# vcf.net
KiCad netlist of a schematic drawn in EAGLE
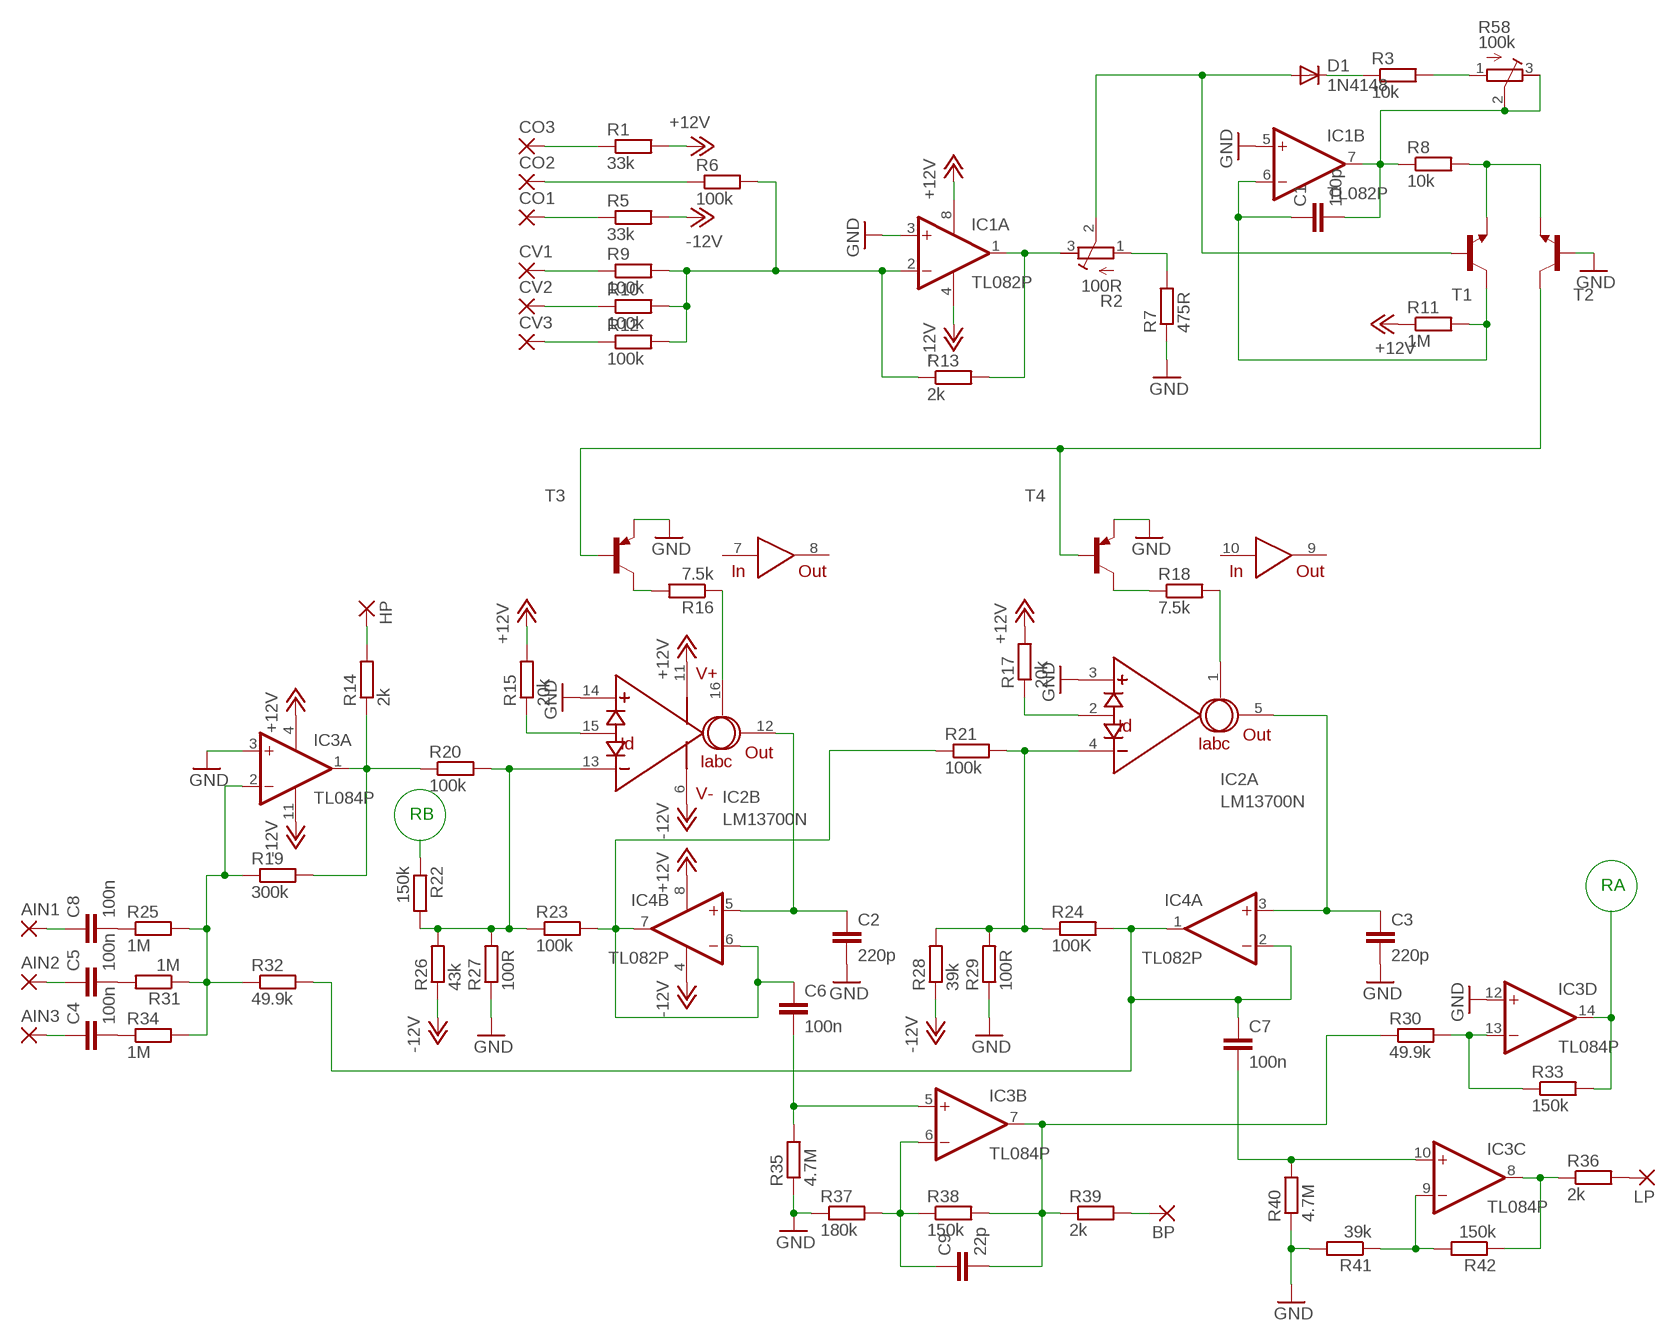
[diagram p0: schematic, sheet 1]
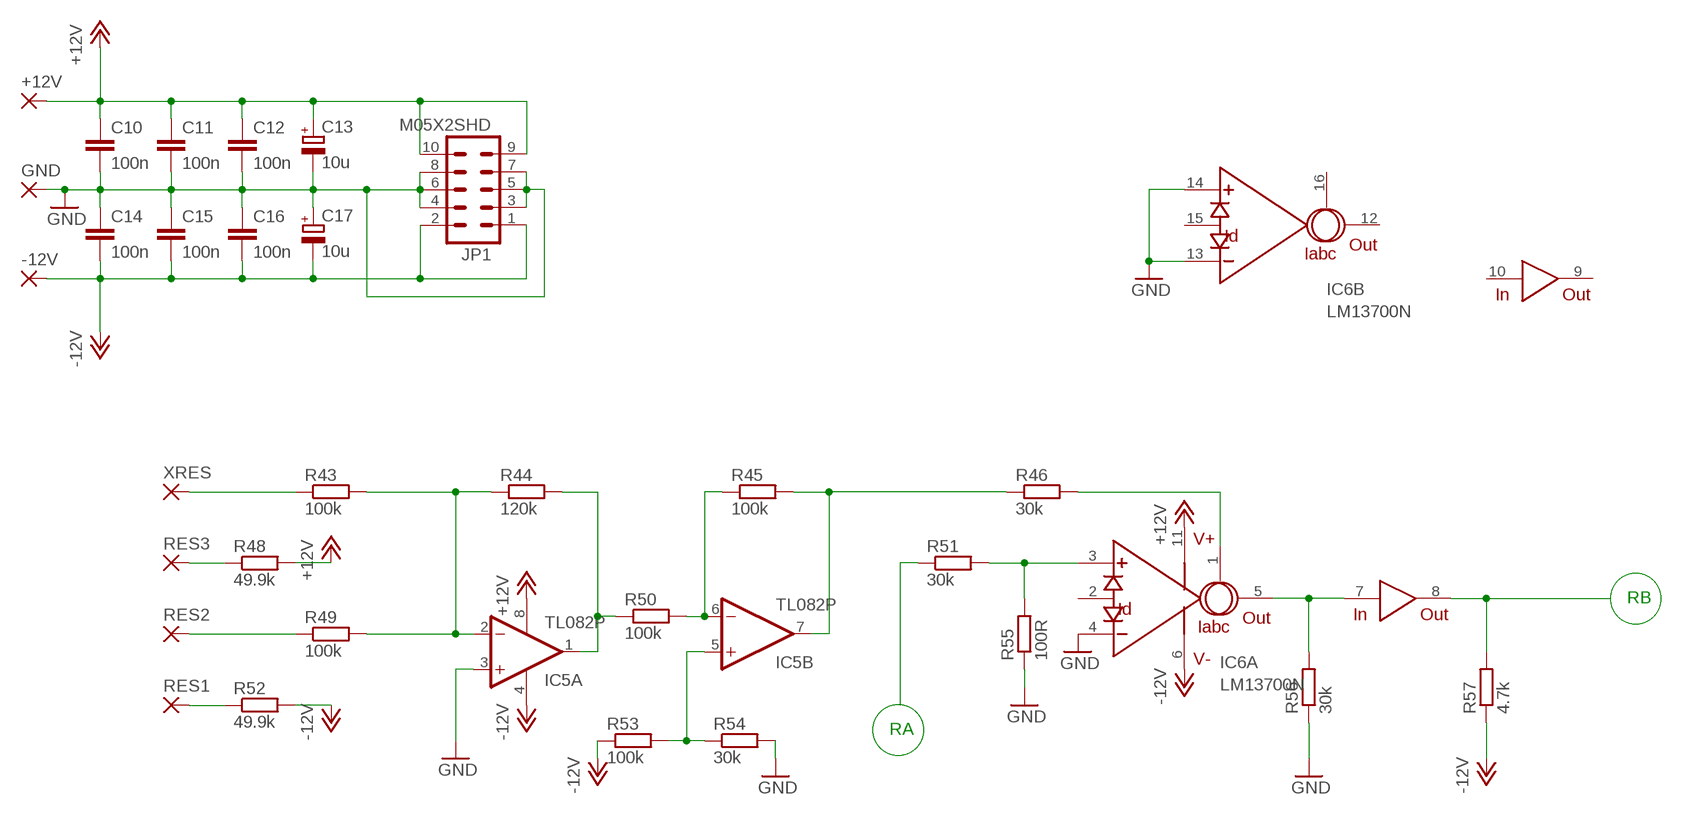
[diagram p1: schematic, sheet 2]

(export (version "E")
  (design (tool "Eeschema 10.0.6"))
  (components
    (comp (ref "+12V")
      (value "2,54/1,0")
      (footprint "eagle-import:2,54_1,0")
      (libsource (lib "eagle-import") (part "2,54/1,0"))
    )
    (comp (ref "-12V")
      (value "2,54/1,0")
      (footprint "eagle-import:2,54_1,0")
      (libsource (lib "eagle-import") (part "2,54/1,0"))
    )
    (comp (ref "C10")
      (value "100n")
      (footprint "eagle-import:C050-035X075")
      (libsource (lib "eagle-import") (part "C-EU050-035X075"))
    )
    (comp (ref "C11")
      (value "100n")
      (footprint "eagle-import:C050-035X075")
      (libsource (lib "eagle-import") (part "C-EU050-035X075"))
    )
    (comp (ref "C12")
      (value "100n")
      (footprint "eagle-import:C050-035X075")
      (libsource (lib "eagle-import") (part "C-EU050-035X075"))
    )
    (comp (ref "C13")
      (value "10u")
      (footprint "eagle-import:E3,5-8")
      (libsource (lib "eagle-import") (part "CPOL-EUE3.5-8"))
    )
    (comp (ref "C14")
      (value "100n")
      (footprint "eagle-import:C050-035X075")
      (libsource (lib "eagle-import") (part "C-EU050-035X075"))
    )
    (comp (ref "C15")
      (value "100n")
      (footprint "eagle-import:C050-035X075")
      (libsource (lib "eagle-import") (part "C-EU050-035X075"))
    )
    (comp (ref "C16")
      (value "100n")
      (footprint "eagle-import:C050-035X075")
      (libsource (lib "eagle-import") (part "C-EU050-035X075"))
    )
    (comp (ref "C17")
      (value "10u")
      (footprint "eagle-import:E3,5-8")
      (libsource (lib "eagle-import") (part "CPOL-EUE3.5-8"))
    )
    (comp (ref "GND")
      (value "2,54/1,0")
      (footprint "eagle-import:2,54_1,0")
      (libsource (lib "eagle-import") (part "2,54/1,0"))
    )
    (comp (ref "IC5")
      (value "TL082P")
      (footprint "eagle-import:DIL08")
      (libsource (lib "eagle-import") (part "TL082P"))
    )
    (comp (ref "IC6")
      (value "LM13700N")
      (footprint "eagle-import:DIL16")
      (libsource (lib "eagle-import") (part "LM13700N"))
    )
    (comp (ref "JP1")
      (value "M05X2SHD")
      (footprint "eagle-import:2X5-SHROUDED")
      (libsource (lib "eagle-import") (part "M05X2SHD"))
    )
    (comp (ref "R43")
      (value "100k")
      (footprint "eagle-import:0309_10")
      (libsource (lib "eagle-import") (part "R-EU_0309/10"))
    )
    (comp (ref "R44")
      (value "120k")
      (footprint "eagle-import:0309_10")
      (libsource (lib "eagle-import") (part "R-EU_0309/10"))
    )
    (comp (ref "R45")
      (value "100k")
      (footprint "eagle-import:0309_10")
      (libsource (lib "eagle-import") (part "R-EU_0309/10"))
    )
    (comp (ref "R46")
      (value "30k")
      (footprint "eagle-import:0309_10")
      (libsource (lib "eagle-import") (part "R-EU_0309/10"))
    )
    (comp (ref "R48")
      (value "49.9k")
      (footprint "eagle-import:0309_10")
      (libsource (lib "eagle-import") (part "R-EU_0309/10"))
    )
    (comp (ref "R49")
      (value "100k")
      (footprint "eagle-import:0309_10")
      (libsource (lib "eagle-import") (part "R-EU_0309/10"))
    )
    (comp (ref "R50")
      (value "100k")
      (footprint "eagle-import:0309_10")
      (libsource (lib "eagle-import") (part "R-EU_0309/10"))
    )
    (comp (ref "R51")
      (value "30k")
      (footprint "eagle-import:0309_10")
      (libsource (lib "eagle-import") (part "R-EU_0309/10"))
    )
    (comp (ref "R52")
      (value "49.9k")
      (footprint "eagle-import:0309_10")
      (libsource (lib "eagle-import") (part "R-EU_0309/10"))
    )
    (comp (ref "R53")
      (value "100k")
      (footprint "eagle-import:0309_10")
      (libsource (lib "eagle-import") (part "R-EU_0309/10"))
    )
    (comp (ref "R54")
      (value "30k")
      (footprint "eagle-import:0309_10")
      (libsource (lib "eagle-import") (part "R-EU_0309/10"))
    )
    (comp (ref "R55")
      (value "100R")
      (footprint "eagle-import:0309_10")
      (libsource (lib "eagle-import") (part "R-EU_0309/10"))
    )
    (comp (ref "R56")
      (value "30k")
      (footprint "eagle-import:0309_10")
      (libsource (lib "eagle-import") (part "R-EU_0309/10"))
    )
    (comp (ref "R57")
      (value "4.7k")
      (footprint "eagle-import:0309_10")
      (libsource (lib "eagle-import") (part "R-EU_0309/10"))
    )
    (comp (ref "RES1")
      (value "2,54/1,0")
      (footprint "eagle-import:2,54_1,0")
      (libsource (lib "eagle-import") (part "2,54/1,0"))
    )
    (comp (ref "RES2")
      (value "2,54/1,0")
      (footprint "eagle-import:2,54_1,0")
      (libsource (lib "eagle-import") (part "2,54/1,0"))
    )
    (comp (ref "RES3")
      (value "2,54/1,0")
      (footprint "eagle-import:2,54_1,0")
      (libsource (lib "eagle-import") (part "2,54/1,0"))
    )
    (comp (ref "XRES")
      (value "2,54/1,0")
      (footprint "eagle-import:2,54_1,0")
      (libsource (lib "eagle-import") (part "2,54/1,0"))
    )
    (comp (ref "AIN1")
      (value "2,54/1,0")
      (footprint "eagle-import:2,54_1,0")
      (libsource (lib "eagle-import") (part "2,54/1,0"))
    )
    (comp (ref "AIN2")
      (value "2,54/1,0")
      (footprint "eagle-import:2,54_1,0")
      (libsource (lib "eagle-import") (part "2,54/1,0"))
    )
    (comp (ref "AIN3")
      (value "2,54/1,0")
      (footprint "eagle-import:2,54_1,0")
      (libsource (lib "eagle-import") (part "2,54/1,0"))
    )
    (comp (ref "BP")
      (value "2,54/1,0")
      (footprint "eagle-import:2,54_1,0")
      (libsource (lib "eagle-import") (part "2,54/1,0"))
    )
    (comp (ref "C1")
      (value "100p")
      (footprint "eagle-import:C050-035X075")
      (libsource (lib "eagle-import") (part "C-EU050-035X075"))
    )
    (comp (ref "C2")
      (value "220p")
      (footprint "eagle-import:C050-035X075")
      (libsource (lib "eagle-import") (part "C-EU050-035X075"))
    )
    (comp (ref "C3")
      (value "220p")
      (footprint "eagle-import:C050-035X075")
      (libsource (lib "eagle-import") (part "C-EU050-035X075"))
    )
    (comp (ref "C4")
      (value "100n")
      (footprint "eagle-import:C050-035X075")
      (libsource (lib "eagle-import") (part "C-EU050-035X075"))
    )
    (comp (ref "C5")
      (value "100n")
      (footprint "eagle-import:C050-035X075")
      (libsource (lib "eagle-import") (part "C-EU050-035X075"))
    )
    (comp (ref "C6")
      (value "100n")
      (footprint "eagle-import:C050-035X075")
      (libsource (lib "eagle-import") (part "C-EU050-035X075"))
    )
    (comp (ref "C7")
      (value "100n")
      (footprint "eagle-import:C050-035X075")
      (libsource (lib "eagle-import") (part "C-EU050-035X075"))
    )
    (comp (ref "C8")
      (value "100n")
      (footprint "eagle-import:C050-035X075")
      (libsource (lib "eagle-import") (part "C-EU050-035X075"))
    )
    (comp (ref "C9")
      (value "22p")
      (footprint "eagle-import:C050-035X075")
      (libsource (lib "eagle-import") (part "C-EU050-035X075"))
    )
    (comp (ref "CO1")
      (value "2,54/1,0")
      (footprint "eagle-import:2,54_1,0")
      (libsource (lib "eagle-import") (part "2,54/1,0"))
    )
    (comp (ref "CO2")
      (value "2,54/1,0")
      (footprint "eagle-import:2,54_1,0")
      (libsource (lib "eagle-import") (part "2,54/1,0"))
    )
    (comp (ref "CO3")
      (value "2,54/1,0")
      (footprint "eagle-import:2,54_1,0")
      (libsource (lib "eagle-import") (part "2,54/1,0"))
    )
    (comp (ref "CV1")
      (value "2,54/1,0")
      (footprint "eagle-import:2,54_1,0")
      (libsource (lib "eagle-import") (part "2,54/1,0"))
    )
    (comp (ref "CV2")
      (value "2,54/1,0")
      (footprint "eagle-import:2,54_1,0")
      (libsource (lib "eagle-import") (part "2,54/1,0"))
    )
    (comp (ref "CV3")
      (value "2,54/1,0")
      (footprint "eagle-import:2,54_1,0")
      (libsource (lib "eagle-import") (part "2,54/1,0"))
    )
    (comp (ref "D1")
      (value "1N4148")
      (footprint "eagle-import:DO35-7")
      (libsource (lib "eagle-import") (part "1N4148DO35-7"))
    )
    (comp (ref "HP")
      (value "2,54/1,0")
      (footprint "eagle-import:2,54_1,0")
      (libsource (lib "eagle-import") (part "2,54/1,0"))
    )
    (comp (ref "IC1")
      (value "TL082P")
      (footprint "eagle-import:DIL08")
      (libsource (lib "eagle-import") (part "TL082P"))
    )
    (comp (ref "IC2")
      (value "LM13700N")
      (footprint "eagle-import:DIL16")
      (libsource (lib "eagle-import") (part "LM13700N"))
    )
    (comp (ref "IC3")
      (value "TL084P")
      (footprint "eagle-import:DIL14")
      (libsource (lib "eagle-import") (part "TL084P"))
    )
    (comp (ref "IC4")
      (value "TL082P")
      (footprint "eagle-import:DIL08")
      (libsource (lib "eagle-import") (part "TL082P"))
    )
    (comp (ref "LP")
      (value "2,54/1,0")
      (footprint "eagle-import:2,54_1,0")
      (libsource (lib "eagle-import") (part "2,54/1,0"))
    )
    (comp (ref "R1")
      (value "33k")
      (footprint "eagle-import:0309V")
      (libsource (lib "eagle-import") (part "R-EU_0309/V"))
    )
    (comp (ref "R2")
      (value "100R")
      (footprint "eagle-import:RTRIM64W")
      (libsource (lib "eagle-import") (part "R-TRIMM64W"))
    )
    (comp (ref "R3")
      (value "10k")
      (footprint "eagle-import:0309V")
      (libsource (lib "eagle-import") (part "R-EU_0309/V"))
    )
    (comp (ref "R5")
      (value "33k")
      (footprint "eagle-import:0309V")
      (libsource (lib "eagle-import") (part "R-EU_0309/V"))
    )
    (comp (ref "R6")
      (value "100k")
      (footprint "eagle-import:0309V")
      (libsource (lib "eagle-import") (part "R-EU_0309/V"))
    )
    (comp (ref "R7")
      (value "475R")
      (footprint "eagle-import:0309V")
      (libsource (lib "eagle-import") (part "R-EU_0309/V"))
    )
    (comp (ref "R8")
      (value "10k")
      (footprint "eagle-import:0309_10")
      (libsource (lib "eagle-import") (part "R-EU_0309/10"))
    )
    (comp (ref "R9")
      (value "100k")
      (footprint "eagle-import:0309V")
      (libsource (lib "eagle-import") (part "R-EU_0309/V"))
    )
    (comp (ref "R10")
      (value "100k")
      (footprint "eagle-import:0309V")
      (libsource (lib "eagle-import") (part "R-EU_0309/V"))
    )
    (comp (ref "R11")
      (value "1M")
      (footprint "eagle-import:0309_10")
      (libsource (lib "eagle-import") (part "R-EU_0309/10"))
    )
    (comp (ref "R12")
      (value "100k")
      (footprint "eagle-import:0309V")
      (libsource (lib "eagle-import") (part "R-EU_0309/V"))
    )
    (comp (ref "R13")
      (value "2k")
      (footprint "eagle-import:0309V")
      (libsource (lib "eagle-import") (part "R-EU_0309/V"))
    )
    (comp (ref "R14")
      (value "2k")
      (footprint "eagle-import:0309V")
      (libsource (lib "eagle-import") (part "R-EU_0309/V"))
    )
    (comp (ref "R15")
      (value "20k")
      (footprint "eagle-import:0309_10")
      (libsource (lib "eagle-import") (part "R-EU_0309/10"))
    )
    (comp (ref "R16")
      (value "7.5k")
      (footprint "eagle-import:0309_10")
      (libsource (lib "eagle-import") (part "R-EU_0309/10"))
    )
    (comp (ref "R17")
      (value "20k")
      (footprint "eagle-import:0309_10")
      (libsource (lib "eagle-import") (part "R-EU_0309/10"))
    )
    (comp (ref "R18")
      (value "7.5k")
      (footprint "eagle-import:0309_10")
      (libsource (lib "eagle-import") (part "R-EU_0309/10"))
    )
    (comp (ref "R19")
      (value "300k")
      (footprint "eagle-import:0309V")
      (libsource (lib "eagle-import") (part "R-EU_0309/V"))
    )
    (comp (ref "R20")
      (value "100k")
      (footprint "eagle-import:0309V")
      (libsource (lib "eagle-import") (part "R-EU_0309/V"))
    )
    (comp (ref "R21")
      (value "100k")
      (footprint "eagle-import:0309_10")
      (libsource (lib "eagle-import") (part "R-EU_0309/10"))
    )
    (comp (ref "R22")
      (value "150k")
      (footprint "eagle-import:0309_10")
      (libsource (lib "eagle-import") (part "R-EU_0309/10"))
    )
    (comp (ref "R23")
      (value "100k")
      (footprint "eagle-import:0309_10")
      (libsource (lib "eagle-import") (part "R-EU_0309/10"))
    )
    (comp (ref "R24")
      (value "100K")
      (footprint "eagle-import:0309_10")
      (libsource (lib "eagle-import") (part "R-EU_0309/10"))
    )
    (comp (ref "R25")
      (value "1M")
      (footprint "eagle-import:0309V")
      (libsource (lib "eagle-import") (part "R-EU_0309/V"))
    )
    (comp (ref "R26")
      (value "43k")
      (footprint "eagle-import:0309V")
      (libsource (lib "eagle-import") (part "R-EU_0309/V"))
    )
    (comp (ref "R27")
      (value "100R")
      (footprint "eagle-import:0309V")
      (libsource (lib "eagle-import") (part "R-EU_0309/V"))
    )
    (comp (ref "R28")
      (value "39k")
      (footprint "eagle-import:0309_10")
      (libsource (lib "eagle-import") (part "R-EU_0309/10"))
    )
    (comp (ref "R29")
      (value "100R")
      (footprint "eagle-import:0309_10")
      (libsource (lib "eagle-import") (part "R-EU_0309/10"))
    )
    (comp (ref "R30")
      (value "49.9k")
      (footprint "eagle-import:0309V")
      (libsource (lib "eagle-import") (part "R-EU_0309/V"))
    )
    (comp (ref "R31")
      (value "1M")
      (footprint "eagle-import:0309V")
      (libsource (lib "eagle-import") (part "R-EU_0309/V"))
    )
    (comp (ref "R32")
      (value "49.9k")
      (footprint "eagle-import:0309_10")
      (libsource (lib "eagle-import") (part "R-EU_0309/10"))
    )
    (comp (ref "R33")
      (value "150k")
      (footprint "eagle-import:0309_10")
      (libsource (lib "eagle-import") (part "R-EU_0309/10"))
    )
    (comp (ref "R34")
      (value "1M")
      (footprint "eagle-import:0309V")
      (libsource (lib "eagle-import") (part "R-EU_0309/V"))
    )
    (comp (ref "R35")
      (value "4.7M")
      (footprint "eagle-import:0309V")
      (libsource (lib "eagle-import") (part "R-EU_0309/V"))
    )
    (comp (ref "R36")
      (value "2k")
      (footprint "eagle-import:0309_10")
      (libsource (lib "eagle-import") (part "R-EU_0309/10"))
    )
    (comp (ref "R37")
      (value "180k")
      (footprint "eagle-import:0309V")
      (libsource (lib "eagle-import") (part "R-EU_0309/V"))
    )
    (comp (ref "R38")
      (value "150k")
      (footprint "eagle-import:0309_10")
      (libsource (lib "eagle-import") (part "R-EU_0309/10"))
    )
    (comp (ref "R39")
      (value "2k")
      (footprint "eagle-import:0309_10")
      (libsource (lib "eagle-import") (part "R-EU_0309/10"))
    )
    (comp (ref "R40")
      (value "4.7M")
      (footprint "eagle-import:0309_10")
      (libsource (lib "eagle-import") (part "R-EU_0309/10"))
    )
    (comp (ref "R41")
      (value "39k")
      (footprint "eagle-import:0309_10")
      (libsource (lib "eagle-import") (part "R-EU_0309/10"))
    )
    (comp (ref "R42")
      (value "150k")
      (footprint "eagle-import:0309_10")
      (libsource (lib "eagle-import") (part "R-EU_0309/10"))
    )
    (comp (ref "R58")
      (value "100k")
      (footprint "eagle-import:RTRIM64W")
      (libsource (lib "eagle-import") (part "R-TRIMM64W"))
    )
    (comp (ref "T1")
      (value "2N3904-NPN-TO92-EBC")
      (footprint "eagle-import:TO92-EBC")
      (libsource (lib "eagle-import") (part "-NPN-TO92-EBC2N3904"))
    )
    (comp (ref "T2")
      (value "2N3904-NPN-TO92-EBC")
      (footprint "eagle-import:TO92-EBC")
      (libsource (lib "eagle-import") (part "-NPN-TO92-EBC2N3904"))
    )
    (comp (ref "T3")
      (value "2N3906-PNP-TO92-EBC")
      (footprint "eagle-import:TO92-EBC")
      (libsource (lib "eagle-import") (part "-PNP-TO92-EBC2N3906"))
    )
    (comp (ref "T4")
      (value "2N3906-PNP-TO92-EBC")
      (footprint "eagle-import:TO92-EBC")
      (libsource (lib "eagle-import") (part "-PNP-TO92-EBC2N3906"))
    )
  )
  (nets
    (net (code "1") (name "+12V") (class "Default")
      (node (ref "+12V") (pin "1") (pinfunction "P_1") (pintype "passive"))
      (node (ref "C10") (pin "1") (pinfunction "1_1") (pintype "passive"))
      (node (ref "C11") (pin "1") (pinfunction "1_1") (pintype "passive"))
      (node (ref "C12") (pin "1") (pinfunction "1_1") (pintype "passive"))
      (node (ref "C13") (pin "+") (pinfunction "+_+") (pintype "passive"))
      (node (ref "IC1") (pin "8") (pinfunction "V+_8") (pintype "power_in"))
      (node (ref "IC2") (pin "11") (pinfunction "V+_11") (pintype "bidirectional"))
      (node (ref "IC3") (pin "4") (pinfunction "V+_4") (pintype "power_in"))
      (node (ref "IC4") (pin "8") (pinfunction "V+_8") (pintype "power_in"))
      (node (ref "IC5") (pin "8") (pinfunction "V+_8") (pintype "power_in"))
      (node (ref "IC6") (pin "11") (pinfunction "V+_11") (pintype "bidirectional"))
      (node (ref "JP1") (pin "10") (pinfunction "10_10") (pintype "passive"))
      (node (ref "JP1") (pin "9") (pinfunction "9_9") (pintype "passive"))
      (node (ref "R1") (pin "2") (pinfunction "2_2") (pintype "passive"))
      (node (ref "R11") (pin "1") (pinfunction "1_1") (pintype "passive"))
      (node (ref "R15") (pin "2") (pinfunction "2_2") (pintype "passive"))
      (node (ref "R17") (pin "2") (pinfunction "2_2") (pintype "passive"))
      (node (ref "R48") (pin "2") (pinfunction "2_2") (pintype "passive"))
    )
    (net (code "2") (name "-12V") (class "Default")
      (node (ref "-12V") (pin "1") (pinfunction "P_1") (pintype "passive"))
      (node (ref "C14") (pin "2") (pinfunction "2_2") (pintype "passive"))
      (node (ref "C15") (pin "2") (pinfunction "2_2") (pintype "passive"))
      (node (ref "C16") (pin "2") (pinfunction "2_2") (pintype "passive"))
      (node (ref "C17") (pin "-") (pinfunction "-_-") (pintype "passive"))
      (node (ref "IC1") (pin "4") (pinfunction "V-_4") (pintype "power_in"))
      (node (ref "IC2") (pin "6") (pinfunction "V-_6") (pintype "bidirectional"))
      (node (ref "IC3") (pin "11") (pinfunction "V-_11") (pintype "power_in"))
      (node (ref "IC4") (pin "4") (pinfunction "V-_4") (pintype "power_in"))
      (node (ref "IC5") (pin "4") (pinfunction "V-_4") (pintype "power_in"))
      (node (ref "IC6") (pin "6") (pinfunction "V-_6") (pintype "bidirectional"))
      (node (ref "JP1") (pin "1") (pinfunction "1_1") (pintype "passive"))
      (node (ref "JP1") (pin "2") (pinfunction "2_2") (pintype "passive"))
      (node (ref "R26") (pin "1") (pinfunction "1_1") (pintype "passive"))
      (node (ref "R28") (pin "1") (pinfunction "1_1") (pintype "passive"))
      (node (ref "R5") (pin "2") (pinfunction "2_2") (pintype "passive"))
      (node (ref "R52") (pin "2") (pinfunction "2_2") (pintype "passive"))
      (node (ref "R53") (pin "1") (pinfunction "1_1") (pintype "passive"))
      (node (ref "R57") (pin "1") (pinfunction "1_1") (pintype "passive"))
    )
    (net (code "3") (name "GND") (class "Default")
      (node (ref "C10") (pin "2") (pinfunction "2_2") (pintype "passive"))
      (node (ref "C11") (pin "2") (pinfunction "2_2") (pintype "passive"))
      (node (ref "C12") (pin "2") (pinfunction "2_2") (pintype "passive"))
      (node (ref "C13") (pin "-") (pinfunction "-_-") (pintype "passive"))
      (node (ref "C14") (pin "1") (pinfunction "1_1") (pintype "passive"))
      (node (ref "C15") (pin "1") (pinfunction "1_1") (pintype "passive"))
      (node (ref "C16") (pin "1") (pinfunction "1_1") (pintype "passive"))
      (node (ref "C17") (pin "+") (pinfunction "+_+") (pintype "passive"))
      (node (ref "C2") (pin "2") (pinfunction "2_2") (pintype "passive"))
      (node (ref "C3") (pin "2") (pinfunction "2_2") (pintype "passive"))
      (node (ref "GND") (pin "1") (pinfunction "P_1") (pintype "passive"))
      (node (ref "IC1") (pin "3") (pinfunction "+IN_3") (pintype "input"))
      (node (ref "IC1") (pin "5") (pinfunction "+IN_5") (pintype "input"))
      (node (ref "IC2") (pin "14") (pinfunction "+IN_14") (pintype "bidirectional"))
      (node (ref "IC2") (pin "3") (pinfunction "+IN_3") (pintype "bidirectional"))
      (node (ref "IC3") (pin "12") (pinfunction "+IN_12") (pintype "input"))
      (node (ref "IC3") (pin "3") (pinfunction "+IN_3") (pintype "input"))
      (node (ref "IC5") (pin "3") (pinfunction "+IN_3") (pintype "input"))
      (node (ref "IC6") (pin "13") (pinfunction "-IN_13") (pintype "bidirectional"))
      (node (ref "IC6") (pin "14") (pinfunction "+IN_14") (pintype "bidirectional"))
      (node (ref "IC6") (pin "4") (pinfunction "-IN_4") (pintype "bidirectional"))
      (node (ref "JP1") (pin "3") (pinfunction "3_3") (pintype "passive"))
      (node (ref "JP1") (pin "4") (pinfunction "4_4") (pintype "passive"))
      (node (ref "JP1") (pin "5") (pinfunction "5_5") (pintype "passive"))
      (node (ref "JP1") (pin "6") (pinfunction "6_6") (pintype "passive"))
      (node (ref "JP1") (pin "7") (pinfunction "7_7") (pintype "passive"))
      (node (ref "JP1") (pin "8") (pinfunction "8_8") (pintype "passive"))
      (node (ref "R27") (pin "1") (pinfunction "1_1") (pintype "passive"))
      (node (ref "R29") (pin "1") (pinfunction "1_1") (pintype "passive"))
      (node (ref "R35") (pin "1") (pinfunction "1_1") (pintype "passive"))
      (node (ref "R37") (pin "1") (pinfunction "1_1") (pintype "passive"))
      (node (ref "R40") (pin "1") (pinfunction "1_1") (pintype "passive"))
      (node (ref "R41") (pin "2") (pinfunction "2_2") (pintype "passive"))
      (node (ref "R54") (pin "2") (pinfunction "2_2") (pintype "passive"))
      (node (ref "R55") (pin "1") (pinfunction "1_1") (pintype "passive"))
      (node (ref "R56") (pin "1") (pinfunction "1_1") (pintype "passive"))
      (node (ref "R7") (pin "1") (pinfunction "1_1") (pintype "passive"))
      (node (ref "T2") (pin "B") (pinfunction "B_B") (pintype "passive"))
      (node (ref "T3") (pin "E") (pinfunction "E_E") (pintype "passive"))
      (node (ref "T4") (pin "E") (pinfunction "E_E") (pintype "passive"))
    )
    (net (code "4") (name "Net-(AIN1-P)") (class "Default")
      (node (ref "AIN1") (pin "1") (pinfunction "P_1") (pintype "passive"))
      (node (ref "C8") (pin "1") (pinfunction "1_1") (pintype "passive"))
    )
    (net (code "5") (name "Net-(AIN2-P)") (class "Default")
      (node (ref "AIN2") (pin "1") (pinfunction "P_1") (pintype "passive"))
      (node (ref "C5") (pin "1") (pinfunction "1_1") (pintype "passive"))
    )
    (net (code "6") (name "Net-(AIN3-P)") (class "Default")
      (node (ref "AIN3") (pin "1") (pinfunction "P_1") (pintype "passive"))
      (node (ref "C4") (pin "1") (pinfunction "1_1") (pintype "passive"))
    )
    (net (code "7") (name "Net-(BP-P)") (class "Default")
      (node (ref "BP") (pin "1") (pinfunction "P_1") (pintype "passive"))
      (node (ref "R39") (pin "2") (pinfunction "2_2") (pintype "passive"))
    )
    (net (code "8") (name "Net-(C4-Pad2)") (class "Default")
      (node (ref "C4") (pin "2") (pinfunction "2_2") (pintype "passive"))
      (node (ref "R34") (pin "1") (pinfunction "1_1") (pintype "passive"))
    )
    (net (code "9") (name "Net-(C5-Pad2)") (class "Default")
      (node (ref "C5") (pin "2") (pinfunction "2_2") (pintype "passive"))
      (node (ref "R31") (pin "2") (pinfunction "2_2") (pintype "passive"))
    )
    (net (code "10") (name "Net-(C8-Pad2)") (class "Default")
      (node (ref "C8") (pin "2") (pinfunction "2_2") (pintype "passive"))
      (node (ref "R25") (pin "1") (pinfunction "1_1") (pintype "passive"))
    )
    (net (code "11") (name "Net-(CO1-P)") (class "Default")
      (node (ref "CO1") (pin "1") (pinfunction "P_1") (pintype "passive"))
      (node (ref "R5") (pin "1") (pinfunction "1_1") (pintype "passive"))
    )
    (net (code "12") (name "Net-(CO2-P)") (class "Default")
      (node (ref "CO2") (pin "1") (pinfunction "P_1") (pintype "passive"))
      (node (ref "R6") (pin "1") (pinfunction "1_1") (pintype "passive"))
    )
    (net (code "13") (name "Net-(CO3-P)") (class "Default")
      (node (ref "CO3") (pin "1") (pinfunction "P_1") (pintype "passive"))
      (node (ref "R1") (pin "1") (pinfunction "1_1") (pintype "passive"))
    )
    (net (code "14") (name "Net-(CV1-P)") (class "Default")
      (node (ref "CV1") (pin "1") (pinfunction "P_1") (pintype "passive"))
      (node (ref "R9") (pin "1") (pinfunction "1_1") (pintype "passive"))
    )
    (net (code "15") (name "Net-(CV2-P)") (class "Default")
      (node (ref "CV2") (pin "1") (pinfunction "P_1") (pintype "passive"))
      (node (ref "R10") (pin "1") (pinfunction "1_1") (pintype "passive"))
    )
    (net (code "16") (name "Net-(CV3-P)") (class "Default")
      (node (ref "CV3") (pin "1") (pinfunction "P_1") (pintype "passive"))
      (node (ref "R12") (pin "1") (pinfunction "1_1") (pintype "passive"))
    )
    (net (code "17") (name "Net-(D1-PadC)") (class "Default")
      (node (ref "D1") (pin "C") (pinfunction "C_C") (pintype "passive"))
      (node (ref "R3") (pin "1") (pinfunction "1_1") (pintype "passive"))
    )
    (net (code "18") (name "Net-(HP-P)") (class "Default")
      (node (ref "HP") (pin "1") (pinfunction "P_1") (pintype "passive"))
      (node (ref "R14") (pin "2") (pinfunction "2_2") (pintype "passive"))
    )
    (net (code "19") (name "Net-(IC1A--IN)") (class "Default")
      (node (ref "IC1") (pin "2") (pinfunction "-IN_2") (pintype "input"))
      (node (ref "R10") (pin "2") (pinfunction "2_2") (pintype "passive"))
      (node (ref "R12") (pin "2") (pinfunction "2_2") (pintype "passive"))
      (node (ref "R13") (pin "1") (pinfunction "1_1") (pintype "passive"))
      (node (ref "R6") (pin "2") (pinfunction "2_2") (pintype "passive"))
      (node (ref "R9") (pin "2") (pinfunction "2_2") (pintype "passive"))
    )
    (net (code "20") (name "Net-(IC1A-OUT)") (class "Default")
      (node (ref "IC1") (pin "1") (pinfunction "OUT_1") (pintype "output"))
      (node (ref "R13") (pin "2") (pinfunction "2_2") (pintype "passive"))
      (node (ref "R2") (pin "3") (pinfunction "E_3") (pintype "passive"))
    )
    (net (code "21") (name "Net-(IC1B--IN)") (class "Default")
      (node (ref "C1") (pin "1") (pinfunction "1_1") (pintype "passive"))
      (node (ref "IC1") (pin "6") (pinfunction "-IN_6") (pintype "input"))
      (node (ref "R11") (pin "2") (pinfunction "2_2") (pintype "passive"))
      (node (ref "T1") (pin "C") (pinfunction "C_C") (pintype "passive"))
    )
    (net (code "22") (name "Net-(IC1B-OUT)") (class "Default")
      (node (ref "C1") (pin "2") (pinfunction "2_2") (pintype "passive"))
      (node (ref "IC1") (pin "7") (pinfunction "OUT_7") (pintype "output"))
      (node (ref "R58") (pin "2") (pinfunction "S_2") (pintype "passive"))
      (node (ref "R58") (pin "3") (pinfunction "E_3") (pintype "passive"))
      (node (ref "R8") (pin "1") (pinfunction "1_1") (pintype "passive"))
    )
    (net (code "23") (name "Net-(IC2A--IN)") (class "Default")
      (node (ref "IC2") (pin "4") (pinfunction "-IN_4") (pintype "bidirectional"))
      (node (ref "R21") (pin "2") (pinfunction "2_2") (pintype "passive"))
      (node (ref "R24") (pin "1") (pinfunction "1_1") (pintype "passive"))
      (node (ref "R28") (pin "2") (pinfunction "2_2") (pintype "passive"))
      (node (ref "R29") (pin "2") (pinfunction "2_2") (pintype "passive"))
    )
    (net (code "24") (name "Net-(IC2A-IABC)") (class "Default")
      (node (ref "IC2") (pin "1") (pinfunction "IABC_1") (pintype "bidirectional"))
      (node (ref "R18") (pin "2") (pinfunction "2_2") (pintype "passive"))
    )
    (net (code "25") (name "Net-(IC2A-ID)") (class "Default")
      (node (ref "IC2") (pin "2") (pinfunction "ID_2") (pintype "bidirectional"))
      (node (ref "R17") (pin "1") (pinfunction "1_1") (pintype "passive"))
    )
    (net (code "26") (name "Net-(IC2A-OUT)") (class "Default")
      (node (ref "C3") (pin "1") (pinfunction "1_1") (pintype "passive"))
      (node (ref "IC2") (pin "5") (pinfunction "OUT_5") (pintype "bidirectional"))
      (node (ref "IC4") (pin "3") (pinfunction "+IN_3") (pintype "input"))
    )
    (net (code "27") (name "Net-(IC2B--IN)") (class "Default")
      (node (ref "IC2") (pin "13") (pinfunction "-IN_13") (pintype "bidirectional"))
      (node (ref "R20") (pin "2") (pinfunction "2_2") (pintype "passive"))
      (node (ref "R22") (pin "2") (pinfunction "2_2") (pintype "passive"))
      (node (ref "R23") (pin "1") (pinfunction "1_1") (pintype "passive"))
      (node (ref "R26") (pin "2") (pinfunction "2_2") (pintype "passive"))
      (node (ref "R27") (pin "2") (pinfunction "2_2") (pintype "passive"))
    )
    (net (code "28") (name "Net-(IC2B-IABC)") (class "Default")
      (node (ref "IC2") (pin "16") (pinfunction "IABC_16") (pintype "bidirectional"))
      (node (ref "R16") (pin "1") (pinfunction "1_1") (pintype "passive"))
    )
    (net (code "29") (name "Net-(IC2B-ID)") (class "Default")
      (node (ref "IC2") (pin "15") (pinfunction "ID_15") (pintype "bidirectional"))
      (node (ref "R15") (pin "1") (pinfunction "1_1") (pintype "passive"))
    )
    (net (code "30") (name "Net-(IC2B-OUT)") (class "Default")
      (node (ref "C2") (pin "1") (pinfunction "1_1") (pintype "passive"))
      (node (ref "IC2") (pin "12") (pinfunction "OUT_12") (pintype "bidirectional"))
      (node (ref "IC4") (pin "5") (pinfunction "+IN_5") (pintype "input"))
    )
    (net (code "31") (name "Net-(IC3A--IN)") (class "Default")
      (node (ref "IC3") (pin "2") (pinfunction "-IN_2") (pintype "input"))
      (node (ref "R19") (pin "1") (pinfunction "1_1") (pintype "passive"))
      (node (ref "R25") (pin "2") (pinfunction "2_2") (pintype "passive"))
      (node (ref "R31") (pin "1") (pinfunction "1_1") (pintype "passive"))
      (node (ref "R32") (pin "1") (pinfunction "1_1") (pintype "passive"))
      (node (ref "R34") (pin "2") (pinfunction "2_2") (pintype "passive"))
    )
    (net (code "32") (name "Net-(IC3A-OUT)") (class "Default")
      (node (ref "IC3") (pin "1") (pinfunction "OUT_1") (pintype "output"))
      (node (ref "R14") (pin "1") (pinfunction "1_1") (pintype "passive"))
      (node (ref "R19") (pin "2") (pinfunction "2_2") (pintype "passive"))
      (node (ref "R20") (pin "1") (pinfunction "1_1") (pintype "passive"))
    )
    (net (code "33") (name "Net-(IC3B-+IN)") (class "Default")
      (node (ref "C6") (pin "2") (pinfunction "2_2") (pintype "passive"))
      (node (ref "IC3") (pin "5") (pinfunction "+IN_5") (pintype "input"))
      (node (ref "R35") (pin "2") (pinfunction "2_2") (pintype "passive"))
    )
    (net (code "34") (name "Net-(IC3B--IN)") (class "Default")
      (node (ref "C9") (pin "1") (pinfunction "1_1") (pintype "passive"))
      (node (ref "IC3") (pin "6") (pinfunction "-IN_6") (pintype "input"))
      (node (ref "R37") (pin "2") (pinfunction "2_2") (pintype "passive"))
      (node (ref "R38") (pin "1") (pinfunction "1_1") (pintype "passive"))
    )
    (net (code "35") (name "Net-(IC3B-OUT)") (class "Default")
      (node (ref "C9") (pin "2") (pinfunction "2_2") (pintype "passive"))
      (node (ref "IC3") (pin "7") (pinfunction "OUT_7") (pintype "output"))
      (node (ref "R30") (pin "1") (pinfunction "1_1") (pintype "passive"))
      (node (ref "R38") (pin "2") (pinfunction "2_2") (pintype "passive"))
      (node (ref "R39") (pin "1") (pinfunction "1_1") (pintype "passive"))
    )
    (net (code "36") (name "Net-(IC3C-+IN)") (class "Default")
      (node (ref "C7") (pin "2") (pinfunction "2_2") (pintype "passive"))
      (node (ref "IC3") (pin "10") (pinfunction "+IN_10") (pintype "input"))
      (node (ref "R40") (pin "2") (pinfunction "2_2") (pintype "passive"))
    )
    (net (code "37") (name "Net-(IC3C--IN)") (class "Default")
      (node (ref "IC3") (pin "9") (pinfunction "-IN_9") (pintype "input"))
      (node (ref "R41") (pin "1") (pinfunction "1_1") (pintype "passive"))
      (node (ref "R42") (pin "2") (pinfunction "2_2") (pintype "passive"))
    )
    (net (code "38") (name "Net-(IC3C-OUT)") (class "Default")
      (node (ref "IC3") (pin "8") (pinfunction "OUT_8") (pintype "output"))
      (node (ref "R36") (pin "1") (pinfunction "1_1") (pintype "passive"))
      (node (ref "R42") (pin "1") (pinfunction "1_1") (pintype "passive"))
    )
    (net (code "39") (name "Net-(IC3D--IN)") (class "Default")
      (node (ref "IC3") (pin "13") (pinfunction "-IN_13") (pintype "input"))
      (node (ref "R30") (pin "2") (pinfunction "2_2") (pintype "passive"))
      (node (ref "R33") (pin "1") (pinfunction "1_1") (pintype "passive"))
    )
    (net (code "40") (name "Net-(IC4A--IN)") (class "Default")
      (node (ref "C7") (pin "1") (pinfunction "1_1") (pintype "passive"))
      (node (ref "IC4") (pin "1") (pinfunction "OUT_1") (pintype "output"))
      (node (ref "IC4") (pin "2") (pinfunction "-IN_2") (pintype "input"))
      (node (ref "R24") (pin "2") (pinfunction "2_2") (pintype "passive"))
      (node (ref "R32") (pin "2") (pinfunction "2_2") (pintype "passive"))
    )
    (net (code "41") (name "Net-(IC4B--IN)") (class "Default")
      (node (ref "C6") (pin "1") (pinfunction "1_1") (pintype "passive"))
      (node (ref "IC4") (pin "6") (pinfunction "-IN_6") (pintype "input"))
      (node (ref "IC4") (pin "7") (pinfunction "OUT_7") (pintype "output"))
      (node (ref "R21") (pin "1") (pinfunction "1_1") (pintype "passive"))
      (node (ref "R23") (pin "2") (pinfunction "2_2") (pintype "passive"))
    )
    (net (code "42") (name "Net-(IC5A--IN)") (class "Default")
      (node (ref "IC5") (pin "2") (pinfunction "-IN_2") (pintype "input"))
      (node (ref "R43") (pin "2") (pinfunction "2_2") (pintype "passive"))
      (node (ref "R44") (pin "1") (pinfunction "1_1") (pintype "passive"))
      (node (ref "R49") (pin "2") (pinfunction "2_2") (pintype "passive"))
    )
    (net (code "43") (name "Net-(IC5A-OUT)") (class "Default")
      (node (ref "IC5") (pin "1") (pinfunction "OUT_1") (pintype "output"))
      (node (ref "R44") (pin "2") (pinfunction "2_2") (pintype "passive"))
      (node (ref "R50") (pin "1") (pinfunction "1_1") (pintype "passive"))
    )
    (net (code "44") (name "Net-(IC5B-+IN)") (class "Default")
      (node (ref "IC5") (pin "5") (pinfunction "+IN_5") (pintype "input"))
      (node (ref "R53") (pin "2") (pinfunction "2_2") (pintype "passive"))
      (node (ref "R54") (pin "1") (pinfunction "1_1") (pintype "passive"))
    )
    (net (code "45") (name "Net-(IC5B--IN)") (class "Default")
      (node (ref "IC5") (pin "6") (pinfunction "-IN_6") (pintype "input"))
      (node (ref "R45") (pin "1") (pinfunction "1_1") (pintype "passive"))
      (node (ref "R50") (pin "2") (pinfunction "2_2") (pintype "passive"))
    )
    (net (code "46") (name "Net-(IC5B-OUT)") (class "Default")
      (node (ref "IC5") (pin "7") (pinfunction "OUT_7") (pintype "output"))
      (node (ref "R45") (pin "2") (pinfunction "2_2") (pintype "passive"))
      (node (ref "R46") (pin "1") (pinfunction "1_1") (pintype "passive"))
    )
    (net (code "47") (name "Net-(IC6A-+IN)") (class "Default")
      (node (ref "IC6") (pin "3") (pinfunction "+IN_3") (pintype "bidirectional"))
      (node (ref "R51") (pin "2") (pinfunction "2_2") (pintype "passive"))
      (node (ref "R55") (pin "2") (pinfunction "2_2") (pintype "passive"))
    )
    (net (code "48") (name "Net-(IC6A-IABC)") (class "Default")
      (node (ref "IC6") (pin "1") (pinfunction "IABC_1") (pintype "bidirectional"))
      (node (ref "R46") (pin "2") (pinfunction "2_2") (pintype "passive"))
    )
    (net (code "49") (name "Net-(IC6A-OUT)") (class "Default")
      (node (ref "IC6") (pin "5") (pinfunction "OUT_5") (pintype "bidirectional"))
      (node (ref "IC6") (pin "7") (pinfunction "IN_7") (pintype "bidirectional"))
      (node (ref "R56") (pin "2") (pinfunction "2_2") (pintype "passive"))
    )
    (net (code "50") (name "Net-(LP-P)") (class "Default")
      (node (ref "LP") (pin "1") (pinfunction "P_1") (pintype "passive"))
      (node (ref "R36") (pin "2") (pinfunction "2_2") (pintype "passive"))
    )
    (net (code "51") (name "Net-(R2-A)") (class "Default")
      (node (ref "R2") (pin "1") (pinfunction "A_1") (pintype "passive"))
      (node (ref "R7") (pin "2") (pinfunction "2_2") (pintype "passive"))
    )
    (net (code "52") (name "Net-(R2-S)") (class "Default")
      (node (ref "D1") (pin "A") (pinfunction "A_A") (pintype "passive"))
      (node (ref "R2") (pin "2") (pinfunction "S_2") (pintype "passive"))
      (node (ref "T1") (pin "B") (pinfunction "B_B") (pintype "passive"))
    )
    (net (code "53") (name "Net-(R8-Pad2)") (class "Default")
      (node (ref "R8") (pin "2") (pinfunction "2_2") (pintype "passive"))
      (node (ref "T1") (pin "E") (pinfunction "E_E") (pintype "passive"))
      (node (ref "T2") (pin "E") (pinfunction "E_E") (pintype "passive"))
    )
    (net (code "54") (name "Net-(R16-Pad2)") (class "Default")
      (node (ref "R16") (pin "2") (pinfunction "2_2") (pintype "passive"))
      (node (ref "T3") (pin "C") (pinfunction "C_C") (pintype "passive"))
    )
    (net (code "55") (name "Net-(R18-Pad1)") (class "Default")
      (node (ref "R18") (pin "1") (pinfunction "1_1") (pintype "passive"))
      (node (ref "T4") (pin "C") (pinfunction "C_C") (pintype "passive"))
    )
    (net (code "56") (name "Net-(R58-A)") (class "Default")
      (node (ref "R3") (pin "2") (pinfunction "2_2") (pintype "passive"))
      (node (ref "R58") (pin "1") (pinfunction "A_1") (pintype "passive"))
    )
    (net (code "57") (name "Net-(RES1-P)") (class "Default")
      (node (ref "R52") (pin "1") (pinfunction "1_1") (pintype "passive"))
      (node (ref "RES1") (pin "1") (pinfunction "P_1") (pintype "passive"))
    )
    (net (code "58") (name "Net-(RES2-P)") (class "Default")
      (node (ref "R49") (pin "1") (pinfunction "1_1") (pintype "passive"))
      (node (ref "RES2") (pin "1") (pinfunction "P_1") (pintype "passive"))
    )
    (net (code "59") (name "Net-(RES3-P)") (class "Default")
      (node (ref "R48") (pin "1") (pinfunction "1_1") (pintype "passive"))
      (node (ref "RES3") (pin "1") (pinfunction "P_1") (pintype "passive"))
    )
    (net (code "60") (name "Net-(T2-PadC)") (class "Default")
      (node (ref "T2") (pin "C") (pinfunction "C_C") (pintype "passive"))
      (node (ref "T3") (pin "B") (pinfunction "B_B") (pintype "passive"))
      (node (ref "T4") (pin "B") (pinfunction "B_B") (pintype "passive"))
    )
    (net (code "61") (name "Net-(XRES-P)") (class "Default")
      (node (ref "R43") (pin "1") (pinfunction "1_1") (pintype "passive"))
      (node (ref "XRES") (pin "1") (pinfunction "P_1") (pintype "passive"))
    )
    (net (code "62") (name "RA") (class "Default")
      (node (ref "IC3") (pin "14") (pinfunction "OUT_14") (pintype "output"))
      (node (ref "R33") (pin "2") (pinfunction "2_2") (pintype "passive"))
      (node (ref "R51") (pin "1") (pinfunction "1_1") (pintype "passive"))
    )
    (net (code "63") (name "RB") (class "Default")
      (node (ref "IC6") (pin "8") (pinfunction "OUT_8") (pintype "bidirectional"))
      (node (ref "R22") (pin "1") (pinfunction "1_1") (pintype "passive"))
      (node (ref "R57") (pin "2") (pinfunction "2_2") (pintype "passive"))
    )
    (net (code "64") (name "unconnected-(IC2C-IN-Pad7)") (class "Default")
      (node (ref "IC2") (pin "7") (pinfunction "IN_7") (pintype "bidirectional"))
    )
    (net (code "65") (name "unconnected-(IC2C-OUT-Pad8)") (class "Default")
      (node (ref "IC2") (pin "8") (pinfunction "OUT_8") (pintype "bidirectional"))
    )
    (net (code "66") (name "unconnected-(IC2D-IN-Pad10)") (class "Default")
      (node (ref "IC2") (pin "10") (pinfunction "IN_10") (pintype "bidirectional"))
    )
    (net (code "67") (name "unconnected-(IC2D-OUT-Pad9)") (class "Default")
      (node (ref "IC2") (pin "9") (pinfunction "OUT_9") (pintype "bidirectional"))
    )
    (net (code "68") (name "unconnected-(IC6A-ID-Pad2)") (class "Default")
      (node (ref "IC6") (pin "2") (pinfunction "ID_2") (pintype "bidirectional"))
    )
    (net (code "69") (name "unconnected-(IC6B-IABC-Pad16)") (class "Default")
      (node (ref "IC6") (pin "16") (pinfunction "IABC_16") (pintype "bidirectional"))
    )
    (net (code "70") (name "unconnected-(IC6B-ID-Pad15)") (class "Default")
      (node (ref "IC6") (pin "15") (pinfunction "ID_15") (pintype "bidirectional"))
    )
    (net (code "71") (name "unconnected-(IC6B-OUT-Pad12)") (class "Default")
      (node (ref "IC6") (pin "12") (pinfunction "OUT_12") (pintype "bidirectional"))
    )
    (net (code "72") (name "unconnected-(IC6D-IN-Pad10)") (class "Default")
      (node (ref "IC6") (pin "10") (pinfunction "IN_10") (pintype "bidirectional"))
    )
    (net (code "73") (name "unconnected-(IC6D-OUT-Pad9)") (class "Default")
      (node (ref "IC6") (pin "9") (pinfunction "OUT_9") (pintype "bidirectional"))
    )
  )
)
